# APC_Sensor.net
KiCad netlist of a schematic drawn in Altium Designer
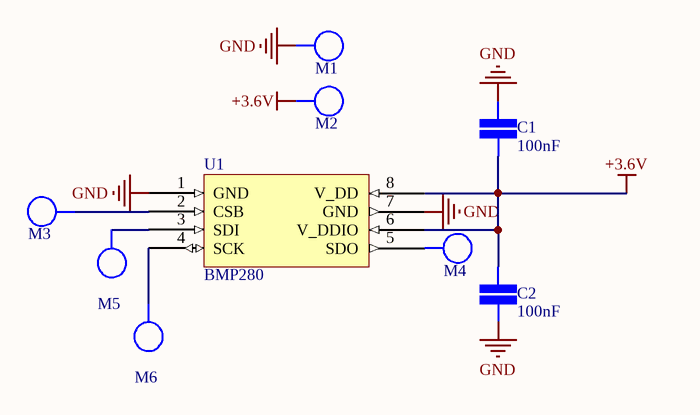
[diagram p0: APC_Sensor.SchDoc]

(export (version "E")
  (design (tool "Eeschema 10.0.6"))
  (components
    (comp (ref "C1")
      (value "100nF")
      (footprint "CAP 0603/1608")
      (description "Capacitor with multiple Footprints")
      (libsource (lib "Standardbauteile") (part "SMD Capacitor"))
    )
    (comp (ref "C2")
      (value "100nF")
      (footprint "CAP 0603/1608")
      (description "Capacitor with multiple Footprints")
      (libsource (lib "") (part "SMD Capacitor_1"))
    )
    (comp (ref "M1")
      (value "mounting pad")
      (footprint "MOUNTING_PAD_M4")
      (libsource (lib "Standardbauteile") (part "mounting pad"))
    )
    (comp (ref "M2")
      (value "mounting pad")
      (footprint "MOUNTING_PAD_M4")
      (libsource (lib "Standardbauteile") (part "mounting pad"))
    )
    (comp (ref "M3")
      (value "mounting pad")
      (footprint "MOUNTING_PAD_M4")
      (libsource (lib "Standardbauteile") (part "mounting pad"))
    )
    (comp (ref "M4")
      (value "mounting pad")
      (footprint "MOUNTING_PAD_M4")
      (libsource (lib "Standardbauteile") (part "mounting pad"))
    )
    (comp (ref "M5")
      (value "mounting pad")
      (footprint "MOUNTING_PAD_M4")
      (libsource (lib "Standardbauteile") (part "mounting pad"))
    )
    (comp (ref "M6")
      (value "mounting pad")
      (footprint "MOUNTING_PAD_M4")
      (libsource (lib "Standardbauteile") (part "mounting pad"))
    )
    (comp (ref "U1")
      (value "BMP280")
      (footprint "LGA 8 Fusch")
      (description "Absolut Pressure Sensor for APC")
      (libsource (lib "Test") (part "BMP280"))
    )
  )
  (nets
    (net (code "1") (name "+3.6V") (class "Default")
      (node (ref "C1") (pin "2") (pinfunction "2_2") (pintype "passive"))
      (node (ref "C2") (pin "2") (pinfunction "2_2") (pintype "passive"))
      (node (ref "M2") (pin "1") (pintype "passive"))
      (node (ref "U1") (pin "6") (pinfunction "V_DDIO_6") (pintype "input"))
      (node (ref "U1") (pin "8") (pinfunction "V_DD_8") (pintype "input"))
    )
    (net (code "2") (name "GND") (class "Default")
      (node (ref "C1") (pin "1") (pinfunction "1_1") (pintype "passive"))
      (node (ref "C2") (pin "1") (pinfunction "1_1") (pintype "passive"))
      (node (ref "M1") (pin "1") (pintype "passive"))
      (node (ref "U1") (pin "1") (pinfunction "GND_1") (pintype "input"))
      (node (ref "U1") (pin "7") (pinfunction "GND_7") (pintype "output"))
    )
    (net (code "3") (name "Net-(U1-CSB)") (class "Default")
      (node (ref "M3") (pin "1") (pintype "passive"))
      (node (ref "U1") (pin "2") (pinfunction "CSB_2") (pintype "input"))
    )
    (net (code "4") (name "Net-(U1-SCK)") (class "Default")
      (node (ref "M6") (pin "1") (pintype "passive"))
      (node (ref "U1") (pin "4") (pinfunction "SCK_4") (pintype "bidirectional"))
    )
    (net (code "5") (name "Net-(U1-SDI)") (class "Default")
      (node (ref "M5") (pin "1") (pintype "passive"))
      (node (ref "U1") (pin "3") (pinfunction "SDI_3") (pintype "input"))
    )
    (net (code "6") (name "Net-(U1-SDO)") (class "Default")
      (node (ref "M4") (pin "1") (pintype "passive"))
      (node (ref "U1") (pin "5") (pinfunction "SDO_5") (pintype "output"))
    )
  )
)
